# SensorBoard.net
KiCad netlist of a schematic drawn in EAGLE
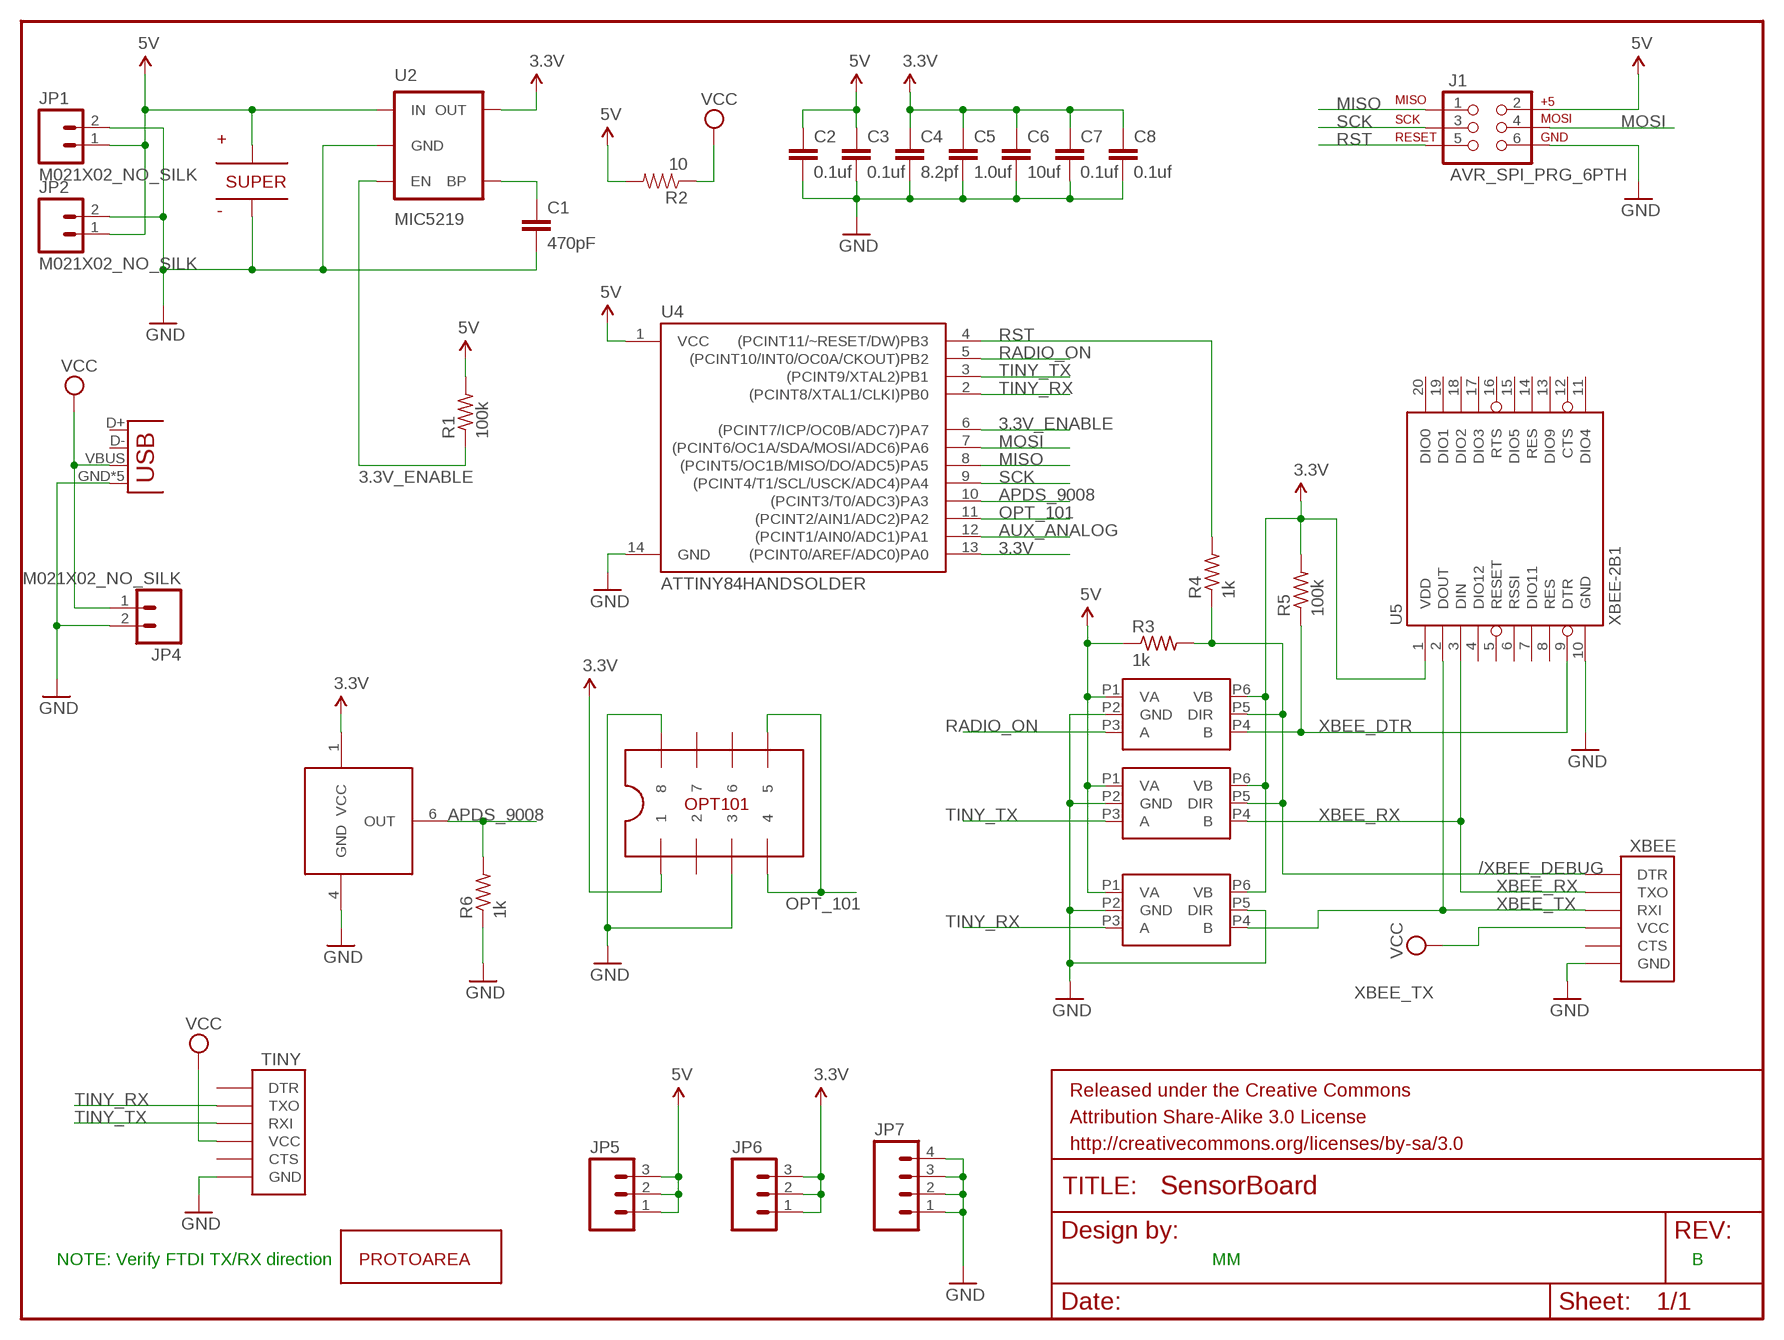
[diagram p0: schematic, sheet 1]

(export (version "E")
  (design (tool "Eeschema 10.0.6"))
  (components
    (comp (ref "C1")
      (value "470pF")
      (footprint "eagle-import:1210")
      (libsource (lib "eagle-import") (part "CAP1210"))
    )
    (comp (ref "C2")
      (value "0.1uf")
      (footprint "eagle-import:1210")
      (libsource (lib "eagle-import") (part "CAP1210"))
    )
    (comp (ref "C3")
      (value "0.1uf")
      (footprint "eagle-import:1210")
      (libsource (lib "eagle-import") (part "CAP1210"))
    )
    (comp (ref "C4")
      (value "8.2pf")
      (footprint "eagle-import:1210")
      (libsource (lib "eagle-import") (part "CAP1210"))
    )
    (comp (ref "C5")
      (value "1.0uf")
      (footprint "eagle-import:1210")
      (libsource (lib "eagle-import") (part "CAP1210"))
    )
    (comp (ref "C6")
      (value "10uf")
      (footprint "eagle-import:1210")
      (libsource (lib "eagle-import") (part "CAP1210"))
    )
    (comp (ref "C7")
      (value "0.1uf")
      (footprint "eagle-import:1210")
      (libsource (lib "eagle-import") (part "CAP1210"))
    )
    (comp (ref "C8")
      (value "0.1uf")
      (footprint "eagle-import:1210")
      (libsource (lib "eagle-import") (part "CAP1210"))
    )
    (comp (ref "FRAME1")
      (value "FRAME-LETTER")
      (footprint "eagle-import:CREATIVE_COMMONS")
      (libsource (lib "eagle-import") (part "FRAME-LETTER"))
    )
    (comp (ref "J1")
      (value "AVR_SPI_PRG_6PTH")
      (footprint "eagle-import:2X3")
      (libsource (lib "eagle-import") (part "AVR_SPI_PRG_6PTH"))
    )
    (comp (ref "JP1")
      (value "M021X02_NO_SILK")
      (footprint "eagle-import:1X02_NO_SILK")
      (libsource (lib "eagle-import") (part "M021X02_NO_SILK"))
    )
    (comp (ref "JP2")
      (value "M021X02_NO_SILK")
      (footprint "eagle-import:1X02_NO_SILK")
      (libsource (lib "eagle-import") (part "M021X02_NO_SILK"))
    )
    (comp (ref "JP3")
      (value "USBSMD")
      (footprint "eagle-import:USB-MINIB")
      (libsource (lib "eagle-import") (part "USBSMD"))
    )
    (comp (ref "JP4")
      (value "M021X02_NO_SILK")
      (footprint "eagle-import:1X02_NO_SILK")
      (libsource (lib "eagle-import") (part "M021X02_NO_SILK"))
    )
    (comp (ref "JP5")
      (value "M031X03_NO_SILK")
      (footprint "eagle-import:1X03_NO_SILK")
      (libsource (lib "eagle-import") (part "M031X03_NO_SILK"))
    )
    (comp (ref "JP6")
      (value "M031X03_NO_SILK")
      (footprint "eagle-import:1X03_NO_SILK")
      (libsource (lib "eagle-import") (part "M031X03_NO_SILK"))
    )
    (comp (ref "JP7")
      (value "M041X04_NO_SILK")
      (footprint "eagle-import:1X04_NO_SILK")
      (libsource (lib "eagle-import") (part "M041X04_NO_SILK"))
    )
    (comp (ref "R1")
      (value "100k")
      (footprint "eagle-import:R1210")
      (libsource (lib "eagle-import") (part "R-US_R1210"))
    )
    (comp (ref "R2")
      (value "10")
      (footprint "eagle-import:AXIAL-0.3")
      (libsource (lib "eagle-import") (part "RESISTORAXIAL-0.3"))
    )
    (comp (ref "R3")
      (value "1k")
      (footprint "eagle-import:R1210")
      (libsource (lib "eagle-import") (part "R-US_R1210"))
    )
    (comp (ref "R4")
      (value "1k")
      (footprint "eagle-import:R1210")
      (libsource (lib "eagle-import") (part "R-US_R1210"))
    )
    (comp (ref "R5")
      (value "100k")
      (footprint "eagle-import:R1210")
      (libsource (lib "eagle-import") (part "R-US_R1210"))
    )
    (comp (ref "R6")
      (value "1k")
      (footprint "eagle-import:R1210")
      (libsource (lib "eagle-import") (part "R-US_R1210"))
    )
    (comp (ref "TINY")
      (value "FTDI_DEVICE")
      (footprint "eagle-import:FTDI_DEVICE_SIDE")
      (libsource (lib "eagle-import") (part "FTDI_DEVICE"))
    )
    (comp (ref "U$1")
      (value "FYD0H225ZF")
      (footprint "eagle-import:SUPERCAP-28.5")
      (libsource (lib "eagle-import") (part "FYD0H225ZF"))
    )
    (comp (ref "U$2")
      (value "PROTOAREA-10X10")
      (footprint "eagle-import:PROTOAREA-10X10")
      (libsource (lib "eagle-import") (part "PROTOAREA-10X10"))
    )
    (comp (ref "U$3")
      (value "SN74LVC1T45")
      (footprint "eagle-import:DBV-R-PDSO-G6")
      (libsource (lib "eagle-import") (part "SN74LVC1T45"))
    )
    (comp (ref "U$4")
      (value "SN74LVC1T45")
      (footprint "eagle-import:DBV-R-PDSO-G6")
      (libsource (lib "eagle-import") (part "SN74LVC1T45"))
    )
    (comp (ref "U$5")
      (value "SN74LVC1T45")
      (footprint "eagle-import:DBV-R-PDSO-G6")
      (libsource (lib "eagle-import") (part "SN74LVC1T45"))
    )
    (comp (ref "U1")
      (value "APDS-9008")
      (footprint "eagle-import:APDS-9008")
      (libsource (lib "eagle-import") (part "APDS-9008"))
    )
    (comp (ref "U2")
      (value "MIC5219")
      (footprint "eagle-import:SOT23-5")
      (libsource (lib "eagle-import") (part "V_REG_MIC52193.3V"))
    )
    (comp (ref "U3")
      (value "OPT101TH")
      (footprint "eagle-import:DIL08")
      (libsource (lib "eagle-import") (part "OPT101TH"))
    )
    (comp (ref "U4")
      (value "ATTINY84HANDSOLDER")
      (footprint "eagle-import:SO14-EZ")
      (libsource (lib "eagle-import") (part "ATTINY84HANDSOLDER"))
    )
    (comp (ref "U5")
      (value "XBEE-2B1")
      (footprint "eagle-import:XBEE-1")
      (libsource (lib "eagle-import") (part "XBEE-2B1"))
    )
    (comp (ref "XBEE")
      (value "FTDI_DEVICE")
      (footprint "eagle-import:FTDI_DEVICE_SIDE")
      (libsource (lib "eagle-import") (part "FTDI_DEVICE"))
    )
  )
  (nets
    (net (code "1") (name "/3.3V_ENABLE") (class "Default")
      (node (ref "R1") (pin "1") (pinfunction "1_1") (pintype "passive"))
      (node (ref "U2") (pin "3") (pinfunction "EN_3") (pintype "input"))
      (node (ref "U4") (pin "6") (pinfunction "(PCINT7/ICP/OC0B/ADC7)PA7_6") (pintype "bidirectional"))
    )
    (net (code "2") (name "/APDS_9008") (class "Default")
      (node (ref "R6") (pin "2") (pinfunction "2_2") (pintype "passive"))
      (node (ref "U1") (pin "6") (pinfunction "OUT_6") (pintype "bidirectional"))
      (node (ref "U4") (pin "10") (pinfunction "(PCINT3/T0/ADC3)PA3_10") (pintype "bidirectional"))
    )
    (net (code "3") (name "/AUX_ANALOG") (class "Default")
      (node (ref "U4") (pin "12") (pinfunction "(PCINT1/AIN0/ADC1)PA1_12") (pintype "bidirectional"))
    )
    (net (code "4") (name "/MISO") (class "Default")
      (node (ref "J1") (pin "1") (pinfunction "1_1") (pintype "passive"))
      (node (ref "U4") (pin "8") (pinfunction "(PCINT5/OC1B/MISO/DO/ADC5)PA5_8") (pintype "bidirectional"))
    )
    (net (code "5") (name "/MOSI") (class "Default")
      (node (ref "J1") (pin "4") (pinfunction "4_4") (pintype "passive"))
      (node (ref "U4") (pin "7") (pinfunction "(PCINT6/OC1A/SDA/MOSI/ADC6)PA6_7") (pintype "bidirectional"))
    )
    (net (code "6") (name "/OPT_101") (class "Default")
      (node (ref "U3") (pin "4") (pinfunction "4_4") (pintype "bidirectional"))
      (node (ref "U3") (pin "5") (pinfunction "5_5") (pintype "bidirectional"))
      (node (ref "U4") (pin "11") (pinfunction "(PCINT2/AIN1/ADC2)PA2_11") (pintype "bidirectional"))
    )
    (net (code "7") (name "/RADIO_ON") (class "Default")
      (node (ref "U$3") (pin "P3") (pinfunction "A_P3") (pintype "bidirectional"))
      (node (ref "U4") (pin "5") (pinfunction "(PCINT10/INT0/OC0A/CKOUT)PB2_5") (pintype "bidirectional"))
    )
    (net (code "8") (name "/RST") (class "Default")
      (node (ref "J1") (pin "5") (pinfunction "5_5") (pintype "passive"))
      (node (ref "R4") (pin "2") (pinfunction "2_2") (pintype "passive"))
      (node (ref "U4") (pin "4") (pinfunction "(PCINT11/~{RESET/DW})PB3_4") (pintype "bidirectional"))
    )
    (net (code "9") (name "/SCK") (class "Default")
      (node (ref "J1") (pin "3") (pinfunction "3_3") (pintype "passive"))
      (node (ref "U4") (pin "9") (pinfunction "(PCINT4/T1/SCL/USCK/ADC4)PA4_9") (pintype "bidirectional"))
    )
    (net (code "10") (name "/TINY_RX") (class "Default")
      (node (ref "TINY") (pin "P$2") (pinfunction "TXO_P$2") (pintype "bidirectional"))
      (node (ref "U$5") (pin "P3") (pinfunction "A_P3") (pintype "bidirectional"))
      (node (ref "U4") (pin "2") (pinfunction "(PCINT8/XTAL1/CLKI)PB0_2") (pintype "bidirectional"))
    )
    (net (code "11") (name "/TINY_TX") (class "Default")
      (node (ref "TINY") (pin "P$3") (pinfunction "RXI_P$3") (pintype "bidirectional"))
      (node (ref "U$4") (pin "P3") (pinfunction "A_P3") (pintype "bidirectional"))
      (node (ref "U4") (pin "3") (pinfunction "(PCINT9/XTAL2)PB1_3") (pintype "bidirectional"))
    )
    (net (code "12") (name "/XBEE_DTR") (class "Default")
      (node (ref "R5") (pin "1") (pinfunction "1_1") (pintype "passive"))
      (node (ref "U$3") (pin "P4") (pinfunction "B_P4") (pintype "bidirectional"))
      (node (ref "U5") (pin "9") (pinfunction "DTR_9") (pintype "bidirectional"))
    )
    (net (code "13") (name "/XBEE_RX") (class "Default")
      (node (ref "U$4") (pin "P4") (pinfunction "B_P4") (pintype "bidirectional"))
      (node (ref "U5") (pin "3") (pinfunction "DIN_3") (pintype "input"))
      (node (ref "XBEE") (pin "P$2") (pinfunction "TXO_P$2") (pintype "bidirectional"))
    )
    (net (code "14") (name "/XBEE_TX") (class "Default")
      (node (ref "U$5") (pin "P4") (pinfunction "B_P4") (pintype "bidirectional"))
      (node (ref "U5") (pin "2") (pinfunction "DOUT_2") (pintype "output"))
      (node (ref "XBEE") (pin "P$3") (pinfunction "RXI_P$3") (pintype "bidirectional"))
    )
    (net (code "15") (name "/{slash}XBEE_DEBUG") (class "Default")
      (node (ref "R3") (pin "2") (pinfunction "2_2") (pintype "passive"))
      (node (ref "R4") (pin "1") (pinfunction "1_1") (pintype "passive"))
      (node (ref "U$3") (pin "P5") (pinfunction "DIR_P5") (pintype "bidirectional"))
      (node (ref "U$4") (pin "P5") (pinfunction "DIR_P5") (pintype "bidirectional"))
      (node (ref "XBEE") (pin "P$1") (pinfunction "DTR_P$1") (pintype "bidirectional"))
    )
    (net (code "16") (name "3.3V") (class "Default")
      (node (ref "C4") (pin "1") (pinfunction "1_1") (pintype "passive"))
      (node (ref "C5") (pin "1") (pinfunction "1_1") (pintype "passive"))
      (node (ref "C6") (pin "1") (pinfunction "1_1") (pintype "passive"))
      (node (ref "C7") (pin "1") (pinfunction "1_1") (pintype "passive"))
      (node (ref "C8") (pin "1") (pinfunction "1_1") (pintype "passive"))
      (node (ref "JP6") (pin "1") (pinfunction "1_1") (pintype "passive"))
      (node (ref "JP6") (pin "2") (pinfunction "2_2") (pintype "passive"))
      (node (ref "JP6") (pin "3") (pinfunction "3_3") (pintype "passive"))
      (node (ref "R5") (pin "2") (pinfunction "2_2") (pintype "passive"))
      (node (ref "U$3") (pin "P6") (pinfunction "VB_P6") (pintype "bidirectional"))
      (node (ref "U$4") (pin "P6") (pinfunction "VB_P6") (pintype "bidirectional"))
      (node (ref "U$5") (pin "P6") (pinfunction "VB_P6") (pintype "bidirectional"))
      (node (ref "U1") (pin "1") (pinfunction "VCC_1") (pintype "bidirectional"))
      (node (ref "U2") (pin "5") (pinfunction "OUT_5") (pintype "passive"))
      (node (ref "U3") (pin "1") (pinfunction "1_1") (pintype "bidirectional"))
      (node (ref "U4") (pin "13") (pinfunction "(PCINT0/AREF/ADC0)PA0_13") (pintype "bidirectional"))
      (node (ref "U5") (pin "1") (pinfunction "VDD_1") (pintype "power_in"))
    )
    (net (code "17") (name "5V") (class "Default")
      (node (ref "C2") (pin "1") (pinfunction "1_1") (pintype "passive"))
      (node (ref "C3") (pin "1") (pinfunction "1_1") (pintype "passive"))
      (node (ref "J1") (pin "2") (pinfunction "2_2") (pintype "passive"))
      (node (ref "JP1") (pin "1") (pinfunction "1_1") (pintype "passive"))
      (node (ref "JP2") (pin "1") (pinfunction "1_1") (pintype "passive"))
      (node (ref "JP5") (pin "1") (pinfunction "1_1") (pintype "passive"))
      (node (ref "JP5") (pin "2") (pinfunction "2_2") (pintype "passive"))
      (node (ref "JP5") (pin "3") (pinfunction "3_3") (pintype "passive"))
      (node (ref "R1") (pin "2") (pinfunction "2_2") (pintype "passive"))
      (node (ref "R2") (pin "P$2") (pinfunction "2_P$2") (pintype "passive"))
      (node (ref "R3") (pin "1") (pinfunction "1_1") (pintype "passive"))
      (node (ref "U$1") (pin "+") (pinfunction "+_+") (pintype "bidirectional"))
      (node (ref "U$3") (pin "P1") (pinfunction "VA_P1") (pintype "bidirectional"))
      (node (ref "U$4") (pin "P1") (pinfunction "VA_P1") (pintype "bidirectional"))
      (node (ref "U$5") (pin "P1") (pinfunction "VA_P1") (pintype "bidirectional"))
      (node (ref "U2") (pin "1") (pinfunction "IN_1") (pintype "input"))
      (node (ref "U4") (pin "1") (pinfunction "VCC_1") (pintype "bidirectional"))
    )
    (net (code "18") (name "GND") (class "Default")
      (node (ref "C1") (pin "2") (pinfunction "2_2") (pintype "passive"))
      (node (ref "C2") (pin "2") (pinfunction "2_2") (pintype "passive"))
      (node (ref "C3") (pin "2") (pinfunction "2_2") (pintype "passive"))
      (node (ref "C4") (pin "2") (pinfunction "2_2") (pintype "passive"))
      (node (ref "C5") (pin "2") (pinfunction "2_2") (pintype "passive"))
      (node (ref "C6") (pin "2") (pinfunction "2_2") (pintype "passive"))
      (node (ref "C7") (pin "2") (pinfunction "2_2") (pintype "passive"))
      (node (ref "C8") (pin "2") (pinfunction "2_2") (pintype "passive"))
      (node (ref "J1") (pin "6") (pinfunction "6_6") (pintype "passive"))
      (node (ref "JP1") (pin "2") (pinfunction "2_2") (pintype "passive"))
      (node (ref "JP2") (pin "2") (pinfunction "2_2") (pintype "passive"))
      (node (ref "JP3") (pin "GND") (pinfunction "GND_GND") (pintype "bidirectional"))
      (node (ref "JP3") (pin "MTN1") (pinfunction "GND_MTN1") (pintype "bidirectional"))
      (node (ref "JP3") (pin "MTN2") (pinfunction "GND_MTN2") (pintype "bidirectional"))
      (node (ref "JP3") (pin "MTN3") (pinfunction "GND_MTN3") (pintype "bidirectional"))
      (node (ref "JP3") (pin "MTN4") (pinfunction "GND_MTN4") (pintype "bidirectional"))
      (node (ref "JP4") (pin "2") (pinfunction "2_2") (pintype "passive"))
      (node (ref "JP7") (pin "1") (pinfunction "1_1") (pintype "passive"))
      (node (ref "JP7") (pin "2") (pinfunction "2_2") (pintype "passive"))
      (node (ref "JP7") (pin "3") (pinfunction "3_3") (pintype "passive"))
      (node (ref "JP7") (pin "4") (pinfunction "4_4") (pintype "passive"))
      (node (ref "R6") (pin "1") (pinfunction "1_1") (pintype "passive"))
      (node (ref "TINY") (pin "P$6") (pinfunction "GND_P$6") (pintype "bidirectional"))
      (node (ref "U$1") (pin "-") (pinfunction "-_-") (pintype "bidirectional"))
      (node (ref "U$3") (pin "P2") (pinfunction "GND_P2") (pintype "bidirectional"))
      (node (ref "U$4") (pin "P2") (pinfunction "GND_P2") (pintype "bidirectional"))
      (node (ref "U$5") (pin "P2") (pinfunction "GND_P2") (pintype "bidirectional"))
      (node (ref "U$5") (pin "P5") (pinfunction "DIR_P5") (pintype "bidirectional"))
      (node (ref "U1") (pin "4") (pinfunction "GND_4") (pintype "bidirectional"))
      (node (ref "U2") (pin "2") (pinfunction "GND_2") (pintype "input"))
      (node (ref "U3") (pin "3") (pinfunction "3_3") (pintype "bidirectional"))
      (node (ref "U3") (pin "8") (pinfunction "8_8") (pintype "bidirectional"))
      (node (ref "U4") (pin "14") (pinfunction "GND_14") (pintype "bidirectional"))
      (node (ref "U5") (pin "10") (pinfunction "GND_10") (pintype "power_in"))
      (node (ref "XBEE") (pin "P$6") (pinfunction "GND_P$6") (pintype "bidirectional"))
    )
    (net (code "19") (name "Net-(U2-BP)") (class "Default")
      (node (ref "C1") (pin "1") (pinfunction "1_1") (pintype "passive"))
      (node (ref "U2") (pin "4") (pinfunction "BP_4") (pintype "input"))
    )
    (net (code "20") (name "VCC") (class "Default")
      (node (ref "JP3") (pin "VBUS") (pinfunction "VBUS_VBUS") (pintype "bidirectional"))
      (node (ref "JP4") (pin "1") (pinfunction "1_1") (pintype "passive"))
      (node (ref "R2") (pin "P$1") (pinfunction "1_P$1") (pintype "passive"))
      (node (ref "TINY") (pin "P$4") (pinfunction "VCC_P$4") (pintype "bidirectional"))
      (node (ref "XBEE") (pin "P$4") (pinfunction "VCC_P$4") (pintype "bidirectional"))
    )
    (net (code "21") (name "unconnected-(JP3-PadD+)") (class "Default")
      (node (ref "JP3") (pin "D+") (pinfunction "D+_D+") (pintype "bidirectional"))
    )
    (net (code "22") (name "unconnected-(JP3-PadD-)") (class "Default")
      (node (ref "JP3") (pin "D-") (pinfunction "D-_D-") (pintype "bidirectional"))
    )
    (net (code "23") (name "unconnected-(TINY-CTS-PadP$5)") (class "Default")
      (node (ref "TINY") (pin "P$5") (pinfunction "CTS_P$5") (pintype "bidirectional"))
    )
    (net (code "24") (name "unconnected-(TINY-DTR-PadP$1)") (class "Default")
      (node (ref "TINY") (pin "P$1") (pinfunction "DTR_P$1") (pintype "bidirectional"))
    )
    (net (code "25") (name "unconnected-(U3-Pad2)") (class "Default")
      (node (ref "U3") (pin "2") (pinfunction "2_2") (pintype "bidirectional"))
    )
    (net (code "26") (name "unconnected-(U3-Pad6)") (class "Default")
      (node (ref "U3") (pin "6") (pinfunction "6_6") (pintype "bidirectional"))
    )
    (net (code "27") (name "unconnected-(U3-Pad7)") (class "Default")
      (node (ref "U3") (pin "7") (pinfunction "7_7") (pintype "bidirectional"))
    )
    (net (code "28") (name "unconnected-(U5-CTS-Pad12)") (class "Default")
      (node (ref "U5") (pin "12") (pinfunction "CTS_12") (pintype "output"))
    )
    (net (code "29") (name "unconnected-(U5-DIO0-Pad20)") (class "Default")
      (node (ref "U5") (pin "20") (pinfunction "DIO0_20") (pintype "bidirectional"))
    )
    (net (code "30") (name "unconnected-(U5-DIO1-Pad19)") (class "Default")
      (node (ref "U5") (pin "19") (pinfunction "DIO1_19") (pintype "bidirectional"))
    )
    (net (code "31") (name "unconnected-(U5-DIO2-Pad18)") (class "Default")
      (node (ref "U5") (pin "18") (pinfunction "DIO2_18") (pintype "bidirectional"))
    )
    (net (code "32") (name "unconnected-(U5-DIO3-Pad17)") (class "Default")
      (node (ref "U5") (pin "17") (pinfunction "DIO3_17") (pintype "bidirectional"))
    )
    (net (code "33") (name "unconnected-(U5-DIO4-Pad11)") (class "Default")
      (node (ref "U5") (pin "11") (pinfunction "DIO4_11") (pintype "bidirectional"))
    )
    (net (code "34") (name "unconnected-(U5-DIO5-Pad15)") (class "Default")
      (node (ref "U5") (pin "15") (pinfunction "DIO5_15") (pintype "bidirectional"))
    )
    (net (code "35") (name "unconnected-(U5-DIO9-Pad13)") (class "Default")
      (node (ref "U5") (pin "13") (pinfunction "DIO9_13") (pintype "bidirectional"))
    )
    (net (code "36") (name "unconnected-(U5-DIO11-Pad7)") (class "Default")
      (node (ref "U5") (pin "7") (pinfunction "DIO11_7") (pintype "bidirectional"))
    )
    (net (code "37") (name "unconnected-(U5-DIO12-Pad4)") (class "Default")
      (node (ref "U5") (pin "4") (pinfunction "DIO12_4") (pintype "bidirectional"))
    )
    (net (code "38") (name "unconnected-(U5-RES-Pad8)") (class "Default")
      (node (ref "U5") (pin "8") (pinfunction "RES_8") (pintype "bidirectional"))
    )
    (net (code "39") (name "unconnected-(U5-RES-Pad14)") (class "Default")
      (node (ref "U5") (pin "14") (pinfunction "RES_14") (pintype "bidirectional"))
    )
    (net (code "40") (name "unconnected-(U5-RESET-Pad5)") (class "Default")
      (node (ref "U5") (pin "5") (pinfunction "RESET_5") (pintype "input"))
    )
    (net (code "41") (name "unconnected-(U5-RSSI-Pad6)") (class "Default")
      (node (ref "U5") (pin "6") (pinfunction "RSSI_6") (pintype "bidirectional"))
    )
    (net (code "42") (name "unconnected-(U5-RTS-Pad16)") (class "Default")
      (node (ref "U5") (pin "16") (pinfunction "RTS_16") (pintype "input"))
    )
    (net (code "43") (name "unconnected-(XBEE-CTS-PadP$5)") (class "Default")
      (node (ref "XBEE") (pin "P$5") (pinfunction "CTS_P$5") (pintype "bidirectional"))
    )
  )
)
